# 04_LMS7002M_Misc.net
KiCad netlist of a schematic drawn in Altium Designer
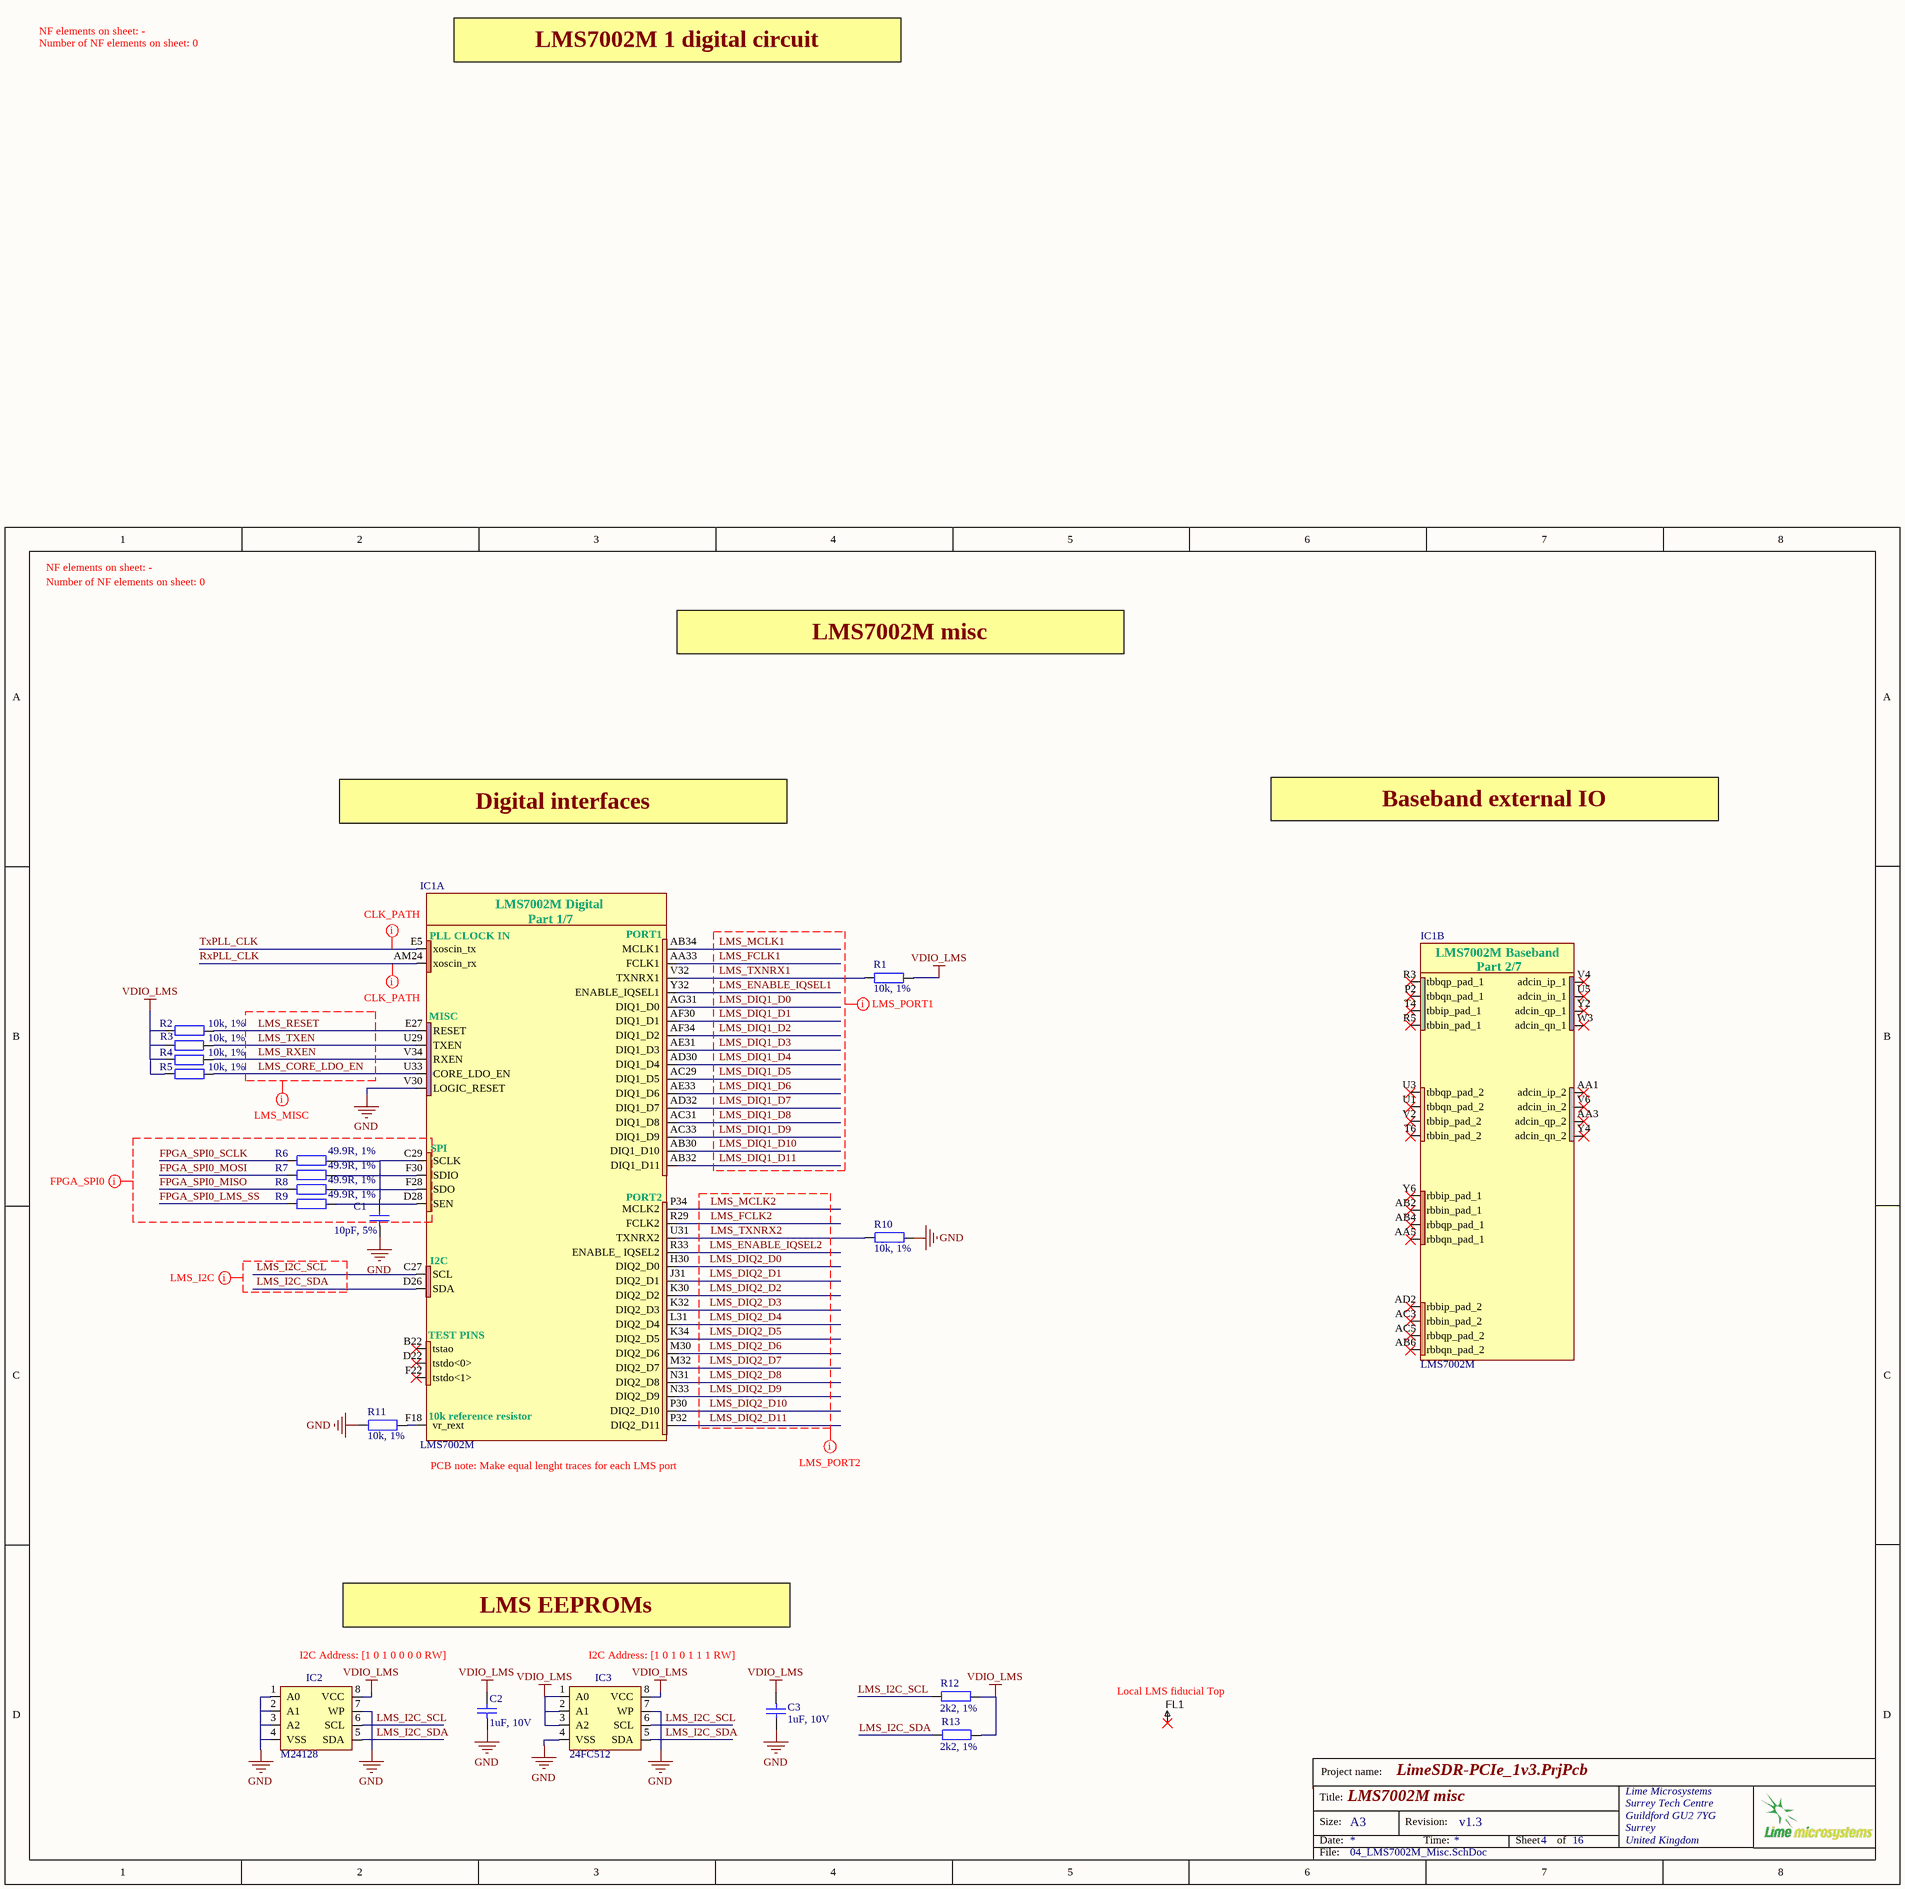
[diagram p0: 04_LMS7002M_Misc.SchDoc]

(export (version "E")
  (design (tool "Eeschema 10.0.6"))
  (components
    (comp (ref "C1")
      (value "10pF, 5%")
      (footprint "CAP0402")
      (fields (field (name "MANUFACTURER") "AVX"))
      (libsource (lib "LimeMicroAltiumLib_schLib") (part "Cap_0402"))
    )
    (comp (ref "C2")
      (value "1uF, 10V")
      (footprint "CAP0402")
      (fields (field (name "MANUFACTURER") "TDK"))
      (libsource (lib "LimeMicroAltiumLib_schLib") (part "Cap_0402"))
    )
    (comp (ref "C3")
      (value "1uF, 10V")
      (footprint "CAP0402")
      (fields (field (name "MANUFACTURER") "TDK"))
      (libsource (lib "LimeMicroAltiumLib_schLib") (part "Cap_0402"))
    )
    (comp (ref "FL1")
      (value "Fiducial")
      (footprint "Fiducial_local")
      (libsource (lib "LimeMicroAltiumLib_schLib") (part "Fiducial"))
    )
    (comp (ref "IC1")
      (value "LMS7002M")
      (footprint "LMS7002M_v2")
      (description "Schematic symbol revision 3. Default footprint - 0.31mm pad")
      (fields (field (name "MANUFACTURER") "Lime Microsystems"))
      (libsource (lib "LimeMicroAltiumLib_schLib") (part "LMS7002Mr3"))
    )
    (comp (ref "IC2")
      (value "M24128")
      (footprint "24FC512")
      (fields (field (name "MANUFACTURER") "STMicroelectronics"))
      (libsource (lib "LimeMicroAltiumLib_schLib") (part "24FC64F"))
    )
    (comp (ref "IC3")
      (value "24FC512")
      (footprint "24FC512")
      (fields (field (name "MANUFACTURER") "Microchip Technology"))
      (libsource (lib "LimeMicroAltiumLib_schLib") (part "24FC512"))
    )
    (comp (ref "R1")
      (value "10k, 1%")
      (footprint "RES0402")
      (fields (field (name "MANUFACTURER") "Yageo") (field (name "TOLERANCE") "±1%"))
      (libsource (lib "LimeMicroAltiumLib_schLib") (part "Res_0402"))
    )
    (comp (ref "R2")
      (value "10k, 1%")
      (footprint "RES0402")
      (fields (field (name "MANUFACTURER") "Yageo") (field (name "TOLERANCE") "±1%"))
      (libsource (lib "LimeMicroAltiumLib_schLib") (part "Res_0402"))
    )
    (comp (ref "R3")
      (value "10k, 1%")
      (footprint "RES0402")
      (fields (field (name "MANUFACTURER") "Yageo") (field (name "TOLERANCE") "±1%"))
      (libsource (lib "LimeMicroAltiumLib_schLib") (part "Res_0402"))
    )
    (comp (ref "R4")
      (value "10k, 1%")
      (footprint "RES0402")
      (fields (field (name "MANUFACTURER") "Yageo") (field (name "TOLERANCE") "±1%"))
      (libsource (lib "LimeMicroAltiumLib_schLib") (part "Res_0402"))
    )
    (comp (ref "R5")
      (value "10k, 1%")
      (footprint "RES0402")
      (fields (field (name "MANUFACTURER") "Yageo") (field (name "TOLERANCE") "±1%"))
      (libsource (lib "LimeMicroAltiumLib_schLib") (part "Res_0402"))
    )
    (comp (ref "R6")
      (value "49.9R, 1%")
      (footprint "RES0402")
      (fields
        (field (name "TOLERANCE") "±1%")
        (field (name "MANUFACTURER") "Samsung Electro-Mechanics America, Inc.")
        (field (name "MANUFACTURER PART NUMBER") "RC1005F49R9CS")
      )
      (libsource (lib "LimeMicroAltiumLib_schLib") (part "Res_0402"))
    )
    (comp (ref "R7")
      (value "49.9R, 1%")
      (footprint "RES0402")
      (fields
        (field (name "TOLERANCE") "±1%")
        (field (name "MANUFACTURER") "Samsung Electro-Mechanics America, Inc.")
        (field (name "MANUFACTURER PART NUMBER") "RC1005F49R9CS")
      )
      (libsource (lib "LimeMicroAltiumLib_schLib") (part "Res_0402"))
    )
    (comp (ref "R8")
      (value "49.9R, 1%")
      (footprint "RES0402")
      (fields
        (field (name "TOLERANCE") "±1%")
        (field (name "MANUFACTURER") "Samsung Electro-Mechanics America, Inc.")
        (field (name "MANUFACTURER PART NUMBER") "RC1005F49R9CS")
      )
      (libsource (lib "LimeMicroAltiumLib_schLib") (part "Res_0402"))
    )
    (comp (ref "R9")
      (value "49.9R, 1%")
      (footprint "RES0402")
      (fields
        (field (name "TOLERANCE") "±1%")
        (field (name "MANUFACTURER") "Samsung Electro-Mechanics America, Inc.")
        (field (name "MANUFACTURER PART NUMBER") "RC1005F49R9CS")
      )
      (libsource (lib "LimeMicroAltiumLib_schLib") (part "Res_0402"))
    )
    (comp (ref "R10")
      (value "10k, 1%")
      (footprint "RES0402")
      (fields (field (name "MANUFACTURER") "Yageo") (field (name "TOLERANCE") "±1%"))
      (libsource (lib "LimeMicroAltiumLib_schLib") (part "Res_0402"))
    )
    (comp (ref "R11")
      (value "10k, 1%")
      (footprint "RES0402")
      (fields (field (name "MANUFACTURER") "Yageo") (field (name "TOLERANCE") "±1%"))
      (libsource (lib "LimeMicroAltiumLib_schLib") (part "Res_0402"))
    )
    (comp (ref "R12")
      (value "2k2, 1%")
      (footprint "RES0402")
      (fields (field (name "MANUFACTURER") "Stackpole Electronics Inc") (field (name "TOLERANCE") "±1%"))
      (libsource (lib "LimeMicroAltiumLib_schLib") (part "Res_0402"))
    )
    (comp (ref "R13")
      (value "2k2, 1%")
      (footprint "RES0402")
      (fields (field (name "MANUFACTURER") "Stackpole Electronics Inc") (field (name "TOLERANCE") "±1%"))
      (libsource (lib "LimeMicroAltiumLib_schLib") (part "Res_0402"))
    )
  )
  (nets
    (net (code "1") (name "/FPGA_SPI0_LMS_SS") (class "Default")
      (node (ref "R9") (pin "2") (pinfunction "2_2") (pintype "passive"))
    )
    (net (code "2") (name "/FPGA_SPI0_MISO") (class "Default")
      (node (ref "R8") (pin "2") (pinfunction "2_2") (pintype "passive"))
    )
    (net (code "3") (name "/FPGA_SPI0_MOSI") (class "Default")
      (node (ref "R7") (pin "2") (pinfunction "2_2") (pintype "passive"))
    )
    (net (code "4") (name "/FPGA_SPI0_SCLK") (class "Default")
      (node (ref "R6") (pin "2") (pinfunction "2_2") (pintype "passive"))
    )
    (net (code "5") (name "/LMS_CORE_LDO_EN") (class "Default")
      (node (ref "IC1") (pin "U33") (pinfunction "CORE_LDO_EN_U33") (pintype "passive"))
      (node (ref "R5") (pin "1") (pinfunction "1_1") (pintype "passive"))
    )
    (net (code "6") (name "/LMS_DIQ1_D0") (class "Default")
      (node (ref "IC1") (pin "AG31") (pinfunction "DIQ1_D0_AG31") (pintype "passive"))
    )
    (net (code "7") (name "/LMS_DIQ1_D1") (class "Default")
      (node (ref "IC1") (pin "AF30") (pinfunction "DIQ1_D1_AF30") (pintype "passive"))
    )
    (net (code "8") (name "/LMS_DIQ1_D2") (class "Default")
      (node (ref "IC1") (pin "AF34") (pinfunction "DIQ1_D2_AF34") (pintype "passive"))
    )
    (net (code "9") (name "/LMS_DIQ1_D3") (class "Default")
      (node (ref "IC1") (pin "AE31") (pinfunction "DIQ1_D3_AE31") (pintype "passive"))
    )
    (net (code "10") (name "/LMS_DIQ1_D4") (class "Default")
      (node (ref "IC1") (pin "AD30") (pinfunction "DIQ1_D4_AD30") (pintype "passive"))
    )
    (net (code "11") (name "/LMS_DIQ1_D5") (class "Default")
      (node (ref "IC1") (pin "AC29") (pinfunction "DIQ1_D5_AC29") (pintype "passive"))
    )
    (net (code "12") (name "/LMS_DIQ1_D6") (class "Default")
      (node (ref "IC1") (pin "AE33") (pinfunction "DIQ1_D6_AE33") (pintype "passive"))
    )
    (net (code "13") (name "/LMS_DIQ1_D7") (class "Default")
      (node (ref "IC1") (pin "AD32") (pinfunction "DIQ1_D7_AD32") (pintype "passive"))
    )
    (net (code "14") (name "/LMS_DIQ1_D8") (class "Default")
      (node (ref "IC1") (pin "AC31") (pinfunction "DIQ1_D8_AC31") (pintype "passive"))
    )
    (net (code "15") (name "/LMS_DIQ1_D9") (class "Default")
      (node (ref "IC1") (pin "AC33") (pinfunction "DIQ1_D9_AC33") (pintype "passive"))
    )
    (net (code "16") (name "/LMS_DIQ1_D10") (class "Default")
      (node (ref "IC1") (pin "AB30") (pinfunction "DIQ1_D10_AB30") (pintype "passive"))
    )
    (net (code "17") (name "/LMS_DIQ1_D11") (class "Default")
      (node (ref "IC1") (pin "AB32") (pinfunction "DIQ1_D11_AB32") (pintype "passive"))
    )
    (net (code "18") (name "/LMS_DIQ2_D0") (class "Default")
      (node (ref "IC1") (pin "H30") (pinfunction "DIQ2_D0_H30") (pintype "passive"))
    )
    (net (code "19") (name "/LMS_DIQ2_D1") (class "Default")
      (node (ref "IC1") (pin "J31") (pinfunction "DIQ2_D1_J31") (pintype "passive"))
    )
    (net (code "20") (name "/LMS_DIQ2_D2") (class "Default")
      (node (ref "IC1") (pin "K30") (pinfunction "DIQ2_D2_K30") (pintype "passive"))
    )
    (net (code "21") (name "/LMS_DIQ2_D3") (class "Default")
      (node (ref "IC1") (pin "K32") (pinfunction "DIQ2_D3_K32") (pintype "passive"))
    )
    (net (code "22") (name "/LMS_DIQ2_D4") (class "Default")
      (node (ref "IC1") (pin "L31") (pinfunction "DIQ2_D4_L31") (pintype "passive"))
    )
    (net (code "23") (name "/LMS_DIQ2_D5") (class "Default")
      (node (ref "IC1") (pin "K34") (pinfunction "DIQ2_D5_K34") (pintype "passive"))
    )
    (net (code "24") (name "/LMS_DIQ2_D6") (class "Default")
      (node (ref "IC1") (pin "M30") (pinfunction "DIQ2_D6_M30") (pintype "passive"))
    )
    (net (code "25") (name "/LMS_DIQ2_D7") (class "Default")
      (node (ref "IC1") (pin "M32") (pinfunction "DIQ2_D7_M32") (pintype "passive"))
    )
    (net (code "26") (name "/LMS_DIQ2_D8") (class "Default")
      (node (ref "IC1") (pin "N31") (pinfunction "DIQ2_D8_N31") (pintype "passive"))
    )
    (net (code "27") (name "/LMS_DIQ2_D9") (class "Default")
      (node (ref "IC1") (pin "N33") (pinfunction "DIQ2_D9_N33") (pintype "passive"))
    )
    (net (code "28") (name "/LMS_DIQ2_D10") (class "Default")
      (node (ref "IC1") (pin "P30") (pinfunction "DIQ2_D10_P30") (pintype "passive"))
    )
    (net (code "29") (name "/LMS_DIQ2_D11") (class "Default")
      (node (ref "IC1") (pin "P32") (pinfunction "DIQ2_D11_P32") (pintype "passive"))
    )
    (net (code "30") (name "/LMS_ENABLE_IQSEL1") (class "Default")
      (node (ref "IC1") (pin "Y32") (pinfunction "ENABLE_IQSEL1_Y32") (pintype "passive"))
    )
    (net (code "31") (name "/LMS_ENABLE_IQSEL2") (class "Default")
      (node (ref "IC1") (pin "R33") (pinfunction "ENABLE__IQSEL2_R33") (pintype "passive"))
    )
    (net (code "32") (name "/LMS_FCLK1") (class "Default")
      (node (ref "IC1") (pin "AA33") (pinfunction "FCLK1_AA33") (pintype "passive"))
    )
    (net (code "33") (name "/LMS_FCLK2") (class "Default")
      (node (ref "IC1") (pin "R29") (pinfunction "FCLK2_R29") (pintype "passive"))
    )
    (net (code "34") (name "/LMS_I2C_SCL") (class "Default")
      (node (ref "IC1") (pin "C27") (pinfunction "SCL_C27") (pintype "passive"))
      (node (ref "IC2") (pin "6") (pinfunction "SCL_6") (pintype "passive"))
      (node (ref "IC3") (pin "6") (pinfunction "SCL_6") (pintype "passive"))
      (node (ref "R12") (pin "2") (pinfunction "2_2") (pintype "passive"))
    )
    (net (code "35") (name "/LMS_I2C_SDA") (class "Default")
      (node (ref "IC1") (pin "D26") (pinfunction "SDA_D26") (pintype "passive"))
      (node (ref "IC2") (pin "5") (pinfunction "SDA_5") (pintype "passive"))
      (node (ref "IC3") (pin "5") (pinfunction "SDA_5") (pintype "passive"))
      (node (ref "R13") (pin "2") (pinfunction "2_2") (pintype "passive"))
    )
    (net (code "36") (name "/LMS_MCLK1") (class "Default")
      (node (ref "IC1") (pin "AB34") (pinfunction "MCLK1_AB34") (pintype "passive"))
    )
    (net (code "37") (name "/LMS_MCLK2") (class "Default")
      (node (ref "IC1") (pin "P34") (pinfunction "MCLK2_P34") (pintype "passive"))
    )
    (net (code "38") (name "/LMS_RESET") (class "Default")
      (node (ref "IC1") (pin "E27") (pinfunction "RESET_E27") (pintype "passive"))
      (node (ref "R2") (pin "1") (pinfunction "1_1") (pintype "passive"))
    )
    (net (code "39") (name "/LMS_RXEN") (class "Default")
      (node (ref "IC1") (pin "V34") (pinfunction "RXEN_V34") (pintype "passive"))
      (node (ref "R4") (pin "2") (pinfunction "2_2") (pintype "passive"))
    )
    (net (code "40") (name "/LMS_TXEN") (class "Default")
      (node (ref "IC1") (pin "U29") (pinfunction "TXEN_U29") (pintype "passive"))
      (node (ref "R3") (pin "2") (pinfunction "2_2") (pintype "passive"))
    )
    (net (code "41") (name "/LMS_TXNRX1") (class "Default")
      (node (ref "IC1") (pin "V32") (pinfunction "TXNRX1_V32") (pintype "passive"))
      (node (ref "R1") (pin "1") (pinfunction "1_1") (pintype "passive"))
    )
    (net (code "42") (name "/LMS_TXNRX2") (class "Default")
      (node (ref "IC1") (pin "U31") (pinfunction "TXNRX2_U31") (pintype "passive"))
      (node (ref "R10") (pin "2") (pinfunction "2_2") (pintype "passive"))
    )
    (net (code "43") (name "/RxPLL_CLK") (class "Default")
      (node (ref "IC1") (pin "AM24") (pinfunction "xoscin_rx_AM24") (pintype "passive"))
    )
    (net (code "44") (name "/TxPLL_CLK") (class "Default")
      (node (ref "IC1") (pin "E5") (pinfunction "xoscin_tx_E5") (pintype "passive"))
    )
    (net (code "45") (name "GND") (class "Default")
      (node (ref "C1") (pin "2") (pinfunction "2_2") (pintype "passive"))
      (node (ref "C2") (pin "2") (pinfunction "2_2") (pintype "passive"))
      (node (ref "C3") (pin "1") (pinfunction "1_1") (pintype "passive"))
      (node (ref "IC1") (pin "V30") (pinfunction "LOGIC_RESET_V30") (pintype "passive"))
      (node (ref "IC2") (pin "1") (pinfunction "A0_1") (pintype "passive"))
      (node (ref "IC2") (pin "2") (pinfunction "A1_2") (pintype "passive"))
      (node (ref "IC2") (pin "3") (pinfunction "A2_3") (pintype "passive"))
      (node (ref "IC2") (pin "4") (pinfunction "VSS_4") (pintype "passive"))
      (node (ref "IC2") (pin "7") (pinfunction "WP_7") (pintype "passive"))
      (node (ref "IC3") (pin "4") (pinfunction "VSS_4") (pintype "passive"))
      (node (ref "IC3") (pin "7") (pinfunction "WP_7") (pintype "passive"))
      (node (ref "R10") (pin "1") (pinfunction "1_1") (pintype "passive"))
      (node (ref "R11") (pin "2") (pinfunction "2_2") (pintype "passive"))
    )
    (net (code "46") (name "Net-(IC1A-SCLK)") (class "Default")
      (node (ref "C1") (pin "1") (pinfunction "1_1") (pintype "passive"))
      (node (ref "IC1") (pin "C29") (pinfunction "SCLK_C29") (pintype "passive"))
      (node (ref "R6") (pin "1") (pinfunction "1_1") (pintype "passive"))
    )
    (net (code "47") (name "Net-(IC1A-SDIO)") (class "Default")
      (node (ref "IC1") (pin "F30") (pinfunction "SDIO_F30") (pintype "passive"))
      (node (ref "R7") (pin "1") (pinfunction "1_1") (pintype "passive"))
    )
    (net (code "48") (name "Net-(IC1A-SDO)") (class "Default")
      (node (ref "IC1") (pin "F28") (pinfunction "SDO_F28") (pintype "passive"))
      (node (ref "R8") (pin "1") (pinfunction "1_1") (pintype "passive"))
    )
    (net (code "49") (name "Net-(IC1A-SEN)") (class "Default")
      (node (ref "IC1") (pin "D28") (pinfunction "SEN_D28") (pintype "passive"))
      (node (ref "R9") (pin "1") (pinfunction "1_1") (pintype "passive"))
    )
    (net (code "50") (name "Net-(IC1A-vr_rext)") (class "Default")
      (node (ref "IC1") (pin "F18") (pinfunction "vr_rext_F18") (pintype "passive"))
      (node (ref "R11") (pin "1") (pinfunction "1_1") (pintype "passive"))
    )
    (net (code "51") (name "VDIO_LMS") (class "Default")
      (node (ref "C2") (pin "1") (pinfunction "1_1") (pintype "passive"))
      (node (ref "C3") (pin "2") (pinfunction "2_2") (pintype "passive"))
      (node (ref "IC2") (pin "8") (pinfunction "VCC_8") (pintype "passive"))
      (node (ref "IC3") (pin "1") (pinfunction "A0_1") (pintype "passive"))
      (node (ref "IC3") (pin "2") (pinfunction "A1_2") (pintype "passive"))
      (node (ref "IC3") (pin "3") (pinfunction "A2_3") (pintype "passive"))
      (node (ref "IC3") (pin "8") (pinfunction "VCC_8") (pintype "passive"))
      (node (ref "R1") (pin "2") (pinfunction "2_2") (pintype "passive"))
      (node (ref "R12") (pin "1") (pinfunction "1_1") (pintype "passive"))
      (node (ref "R13") (pin "1") (pinfunction "1_1") (pintype "passive"))
      (node (ref "R2") (pin "2") (pinfunction "2_2") (pintype "passive"))
      (node (ref "R3") (pin "1") (pinfunction "1_1") (pintype "passive"))
      (node (ref "R4") (pin "1") (pinfunction "1_1") (pintype "passive"))
      (node (ref "R5") (pin "2") (pinfunction "2_2") (pintype "passive"))
    )
    (net (code "52") (name "unconnected-(FL1-Pad1)") (class "Default")
      (node (ref "FL1") (pin "1") (pintype "passive+no_connect"))
    )
    (net (code "53") (name "unconnected-(IC1A-tstao-PadB22)") (class "Default")
      (node (ref "IC1") (pin "B22") (pinfunction "tstao_B22") (pintype "passive+no_connect"))
    )
    (net (code "54") (name "unconnected-(IC1A-tstdo<0>-PadD22)") (class "Default")
      (node (ref "IC1") (pin "D22") (pinfunction "tstdo<0>_D22") (pintype "passive+no_connect"))
    )
    (net (code "55") (name "unconnected-(IC1A-tstdo<1>-PadF22)") (class "Default")
      (node (ref "IC1") (pin "F22") (pinfunction "tstdo<1>_F22") (pintype "passive+no_connect"))
    )
    (net (code "56") (name "unconnected-(IC1B-adcin_in_1-PadU5)") (class "Default")
      (node (ref "IC1") (pin "U5") (pinfunction "adcin_in_1_U5") (pintype "passive+no_connect"))
    )
    (net (code "57") (name "unconnected-(IC1B-adcin_in_2-PadV6)") (class "Default")
      (node (ref "IC1") (pin "V6") (pinfunction "adcin_in_2_V6") (pintype "passive+no_connect"))
    )
    (net (code "58") (name "unconnected-(IC1B-adcin_ip_1-PadV4)") (class "Default")
      (node (ref "IC1") (pin "V4") (pinfunction "adcin_ip_1_V4") (pintype "passive+no_connect"))
    )
    (net (code "59") (name "unconnected-(IC1B-adcin_ip_2-PadAA1)") (class "Default")
      (node (ref "IC1") (pin "AA1") (pinfunction "adcin_ip_2_AA1") (pintype "passive+no_connect"))
    )
    (net (code "60") (name "unconnected-(IC1B-adcin_qn_1-PadW3)") (class "Default")
      (node (ref "IC1") (pin "W3") (pinfunction "adcin_qn_1_W3") (pintype "passive+no_connect"))
    )
    (net (code "61") (name "unconnected-(IC1B-adcin_qn_2-PadY4)") (class "Default")
      (node (ref "IC1") (pin "Y4") (pinfunction "adcin_qn_2_Y4") (pintype "passive+no_connect"))
    )
    (net (code "62") (name "unconnected-(IC1B-adcin_qp_1-PadY2)") (class "Default")
      (node (ref "IC1") (pin "Y2") (pinfunction "adcin_qp_1_Y2") (pintype "passive+no_connect"))
    )
    (net (code "63") (name "unconnected-(IC1B-adcin_qp_2-PadAA3)") (class "Default")
      (node (ref "IC1") (pin "AA3") (pinfunction "adcin_qp_2_AA3") (pintype "passive+no_connect"))
    )
    (net (code "64") (name "unconnected-(IC1B-rbbin_pad_1-PadAB2)") (class "Default")
      (node (ref "IC1") (pin "AB2") (pinfunction "rbbin_pad_1_AB2") (pintype "passive+no_connect"))
    )
    (net (code "65") (name "unconnected-(IC1B-rbbin_pad_2-PadAC3)") (class "Default")
      (node (ref "IC1") (pin "AC3") (pinfunction "rbbin_pad_2_AC3") (pintype "passive+no_connect"))
    )
    (net (code "66") (name "unconnected-(IC1B-rbbip_pad_1-PadY6)") (class "Default")
      (node (ref "IC1") (pin "Y6") (pinfunction "rbbip_pad_1_Y6") (pintype "passive+no_connect"))
    )
    (net (code "67") (name "unconnected-(IC1B-rbbip_pad_2-PadAD2)") (class "Default")
      (node (ref "IC1") (pin "AD2") (pinfunction "rbbip_pad_2_AD2") (pintype "passive+no_connect"))
    )
    (net (code "68") (name "unconnected-(IC1B-rbbqn_pad_1-PadAA5)") (class "Default")
      (node (ref "IC1") (pin "AA5") (pinfunction "rbbqn_pad_1_AA5") (pintype "passive+no_connect"))
    )
    (net (code "69") (name "unconnected-(IC1B-rbbqn_pad_2-PadAB6)") (class "Default")
      (node (ref "IC1") (pin "AB6") (pinfunction "rbbqn_pad_2_AB6") (pintype "passive+no_connect"))
    )
    (net (code "70") (name "unconnected-(IC1B-rbbqp_pad_1-PadAB4)") (class "Default")
      (node (ref "IC1") (pin "AB4") (pinfunction "rbbqp_pad_1_AB4") (pintype "passive+no_connect"))
    )
    (net (code "71") (name "unconnected-(IC1B-rbbqp_pad_2-PadAC5)") (class "Default")
      (node (ref "IC1") (pin "AC5") (pinfunction "rbbqp_pad_2_AC5") (pintype "passive+no_connect"))
    )
    (net (code "72") (name "unconnected-(IC1B-tbbin_pad_1-PadR5)") (class "Default")
      (node (ref "IC1") (pin "R5") (pinfunction "tbbin_pad_1_R5") (pintype "passive+no_connect"))
    )
    (net (code "73") (name "unconnected-(IC1B-tbbin_pad_2-PadT6)") (class "Default")
      (node (ref "IC1") (pin "T6") (pinfunction "tbbin_pad_2_T6") (pintype "passive+no_connect"))
    )
    (net (code "74") (name "unconnected-(IC1B-tbbip_pad_1-PadT4)") (class "Default")
      (node (ref "IC1") (pin "T4") (pinfunction "tbbip_pad_1_T4") (pintype "passive+no_connect"))
    )
    (net (code "75") (name "unconnected-(IC1B-tbbip_pad_2-PadV2)") (class "Default")
      (node (ref "IC1") (pin "V2") (pinfunction "tbbip_pad_2_V2") (pintype "passive+no_connect"))
    )
    (net (code "76") (name "unconnected-(IC1B-tbbqn_pad_1-PadP2)") (class "Default")
      (node (ref "IC1") (pin "P2") (pinfunction "tbbqn_pad_1_P2") (pintype "passive+no_connect"))
    )
    (net (code "77") (name "unconnected-(IC1B-tbbqn_pad_2-PadU1)") (class "Default")
      (node (ref "IC1") (pin "U1") (pinfunction "tbbqn_pad_2_U1") (pintype "passive+no_connect"))
    )
    (net (code "78") (name "unconnected-(IC1B-tbbqp_pad_1-PadR3)") (class "Default")
      (node (ref "IC1") (pin "R3") (pinfunction "tbbqp_pad_1_R3") (pintype "passive+no_connect"))
    )
    (net (code "79") (name "unconnected-(IC1B-tbbqp_pad_2-PadU3)") (class "Default")
      (node (ref "IC1") (pin "U3") (pinfunction "tbbqp_pad_2_U3") (pintype "passive+no_connect"))
    )
  )
)
